# ESP32_mini_4L.net
KiCad netlist of a schematic drawn in EAGLE
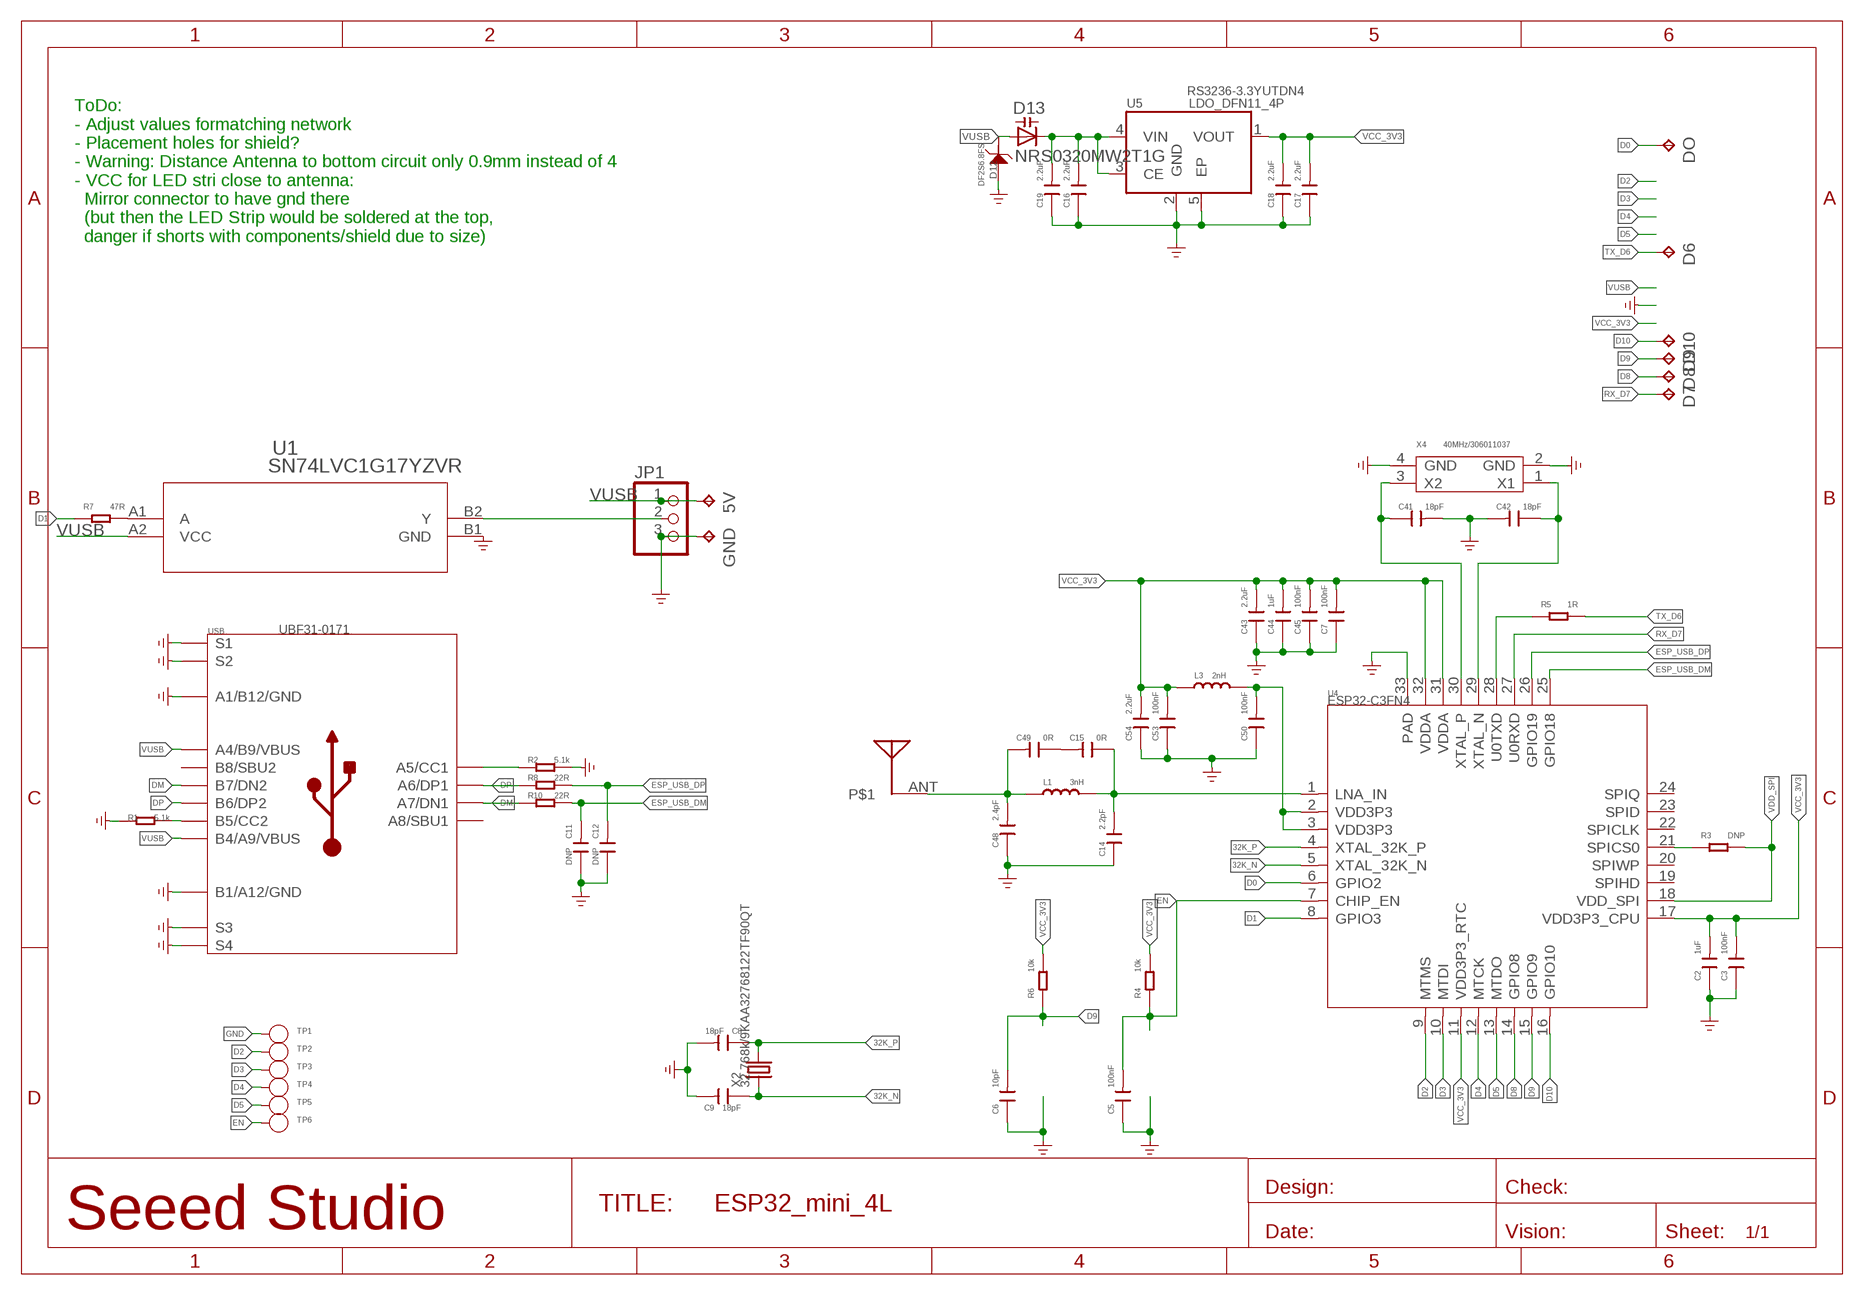
[diagram p0: schematic, sheet 1]

(export (version "E")
  (design (tool "Eeschema 10.0.6"))
  (components
    (comp (ref "5V")
      (value "TPTP07R")
      (footprint "eagle-import:TP07R")
      (libsource (lib "eagle-import") (part "TPTP07R"))
    )
    (comp (ref "C2")
      (value "1uF")
      (footprint "eagle-import:C0201")
      (libsource (lib "eagle-import") (part "CAP-0201"))
    )
    (comp (ref "C3")
      (value "100nF")
      (footprint "eagle-import:C0201")
      (libsource (lib "eagle-import") (part "CAP-0201"))
    )
    (comp (ref "C5")
      (value "100nF")
      (footprint "eagle-import:C0201")
      (libsource (lib "eagle-import") (part "CAP-0201"))
    )
    (comp (ref "C6")
      (value "10pF")
      (footprint "eagle-import:C0201")
      (libsource (lib "eagle-import") (part "CAP-0201"))
    )
    (comp (ref "C7")
      (value "100nF")
      (footprint "eagle-import:C0201")
      (libsource (lib "eagle-import") (part "CAP-0201"))
    )
    (comp (ref "C8")
      (value "18pF")
      (footprint "eagle-import:C0201")
      (libsource (lib "eagle-import") (part "CAP-0201"))
    )
    (comp (ref "C9")
      (value "18pF")
      (footprint "eagle-import:C0201")
      (libsource (lib "eagle-import") (part "CAP-0201"))
    )
    (comp (ref "C11")
      (value "DNP")
      (footprint "eagle-import:C0201")
      (libsource (lib "eagle-import") (part "CAP-0201"))
    )
    (comp (ref "C12")
      (value "DNP")
      (footprint "eagle-import:C0201")
      (libsource (lib "eagle-import") (part "CAP-0201"))
    )
    (comp (ref "C14")
      (value "2.2pF")
      (footprint "eagle-import:C0201")
      (libsource (lib "eagle-import") (part "CAP-0201"))
    )
    (comp (ref "C15")
      (value "0R")
      (footprint "eagle-import:C0201")
      (libsource (lib "eagle-import") (part "CAP-0201"))
    )
    (comp (ref "C16")
      (value "2.2uF")
      (footprint "eagle-import:C0201")
      (libsource (lib "eagle-import") (part "CAP-0201"))
    )
    (comp (ref "C17")
      (value "2.2uF")
      (footprint "eagle-import:C0201")
      (libsource (lib "eagle-import") (part "CAP-0201"))
    )
    (comp (ref "C18")
      (value "2.2uF")
      (footprint "eagle-import:C0201")
      (libsource (lib "eagle-import") (part "CAP-0201"))
    )
    (comp (ref "C19")
      (value "2.2uF")
      (footprint "eagle-import:C0201")
      (libsource (lib "eagle-import") (part "CAP-0201"))
    )
    (comp (ref "C41")
      (value "18pF")
      (footprint "eagle-import:C0201")
      (libsource (lib "eagle-import") (part "CAP-0201"))
    )
    (comp (ref "C42")
      (value "18pF")
      (footprint "eagle-import:C0201")
      (libsource (lib "eagle-import") (part "CAP-0201"))
    )
    (comp (ref "C43")
      (value "2.2uF")
      (footprint "eagle-import:C0201")
      (libsource (lib "eagle-import") (part "CAP-0201"))
    )
    (comp (ref "C44")
      (value "1uF")
      (footprint "eagle-import:C0201")
      (libsource (lib "eagle-import") (part "CAP-0201"))
    )
    (comp (ref "C45")
      (value "100nF")
      (footprint "eagle-import:C0201")
      (libsource (lib "eagle-import") (part "CAP-0201"))
    )
    (comp (ref "C48")
      (value "2.4pF")
      (footprint "eagle-import:C0201")
      (libsource (lib "eagle-import") (part "CAP-0201"))
    )
    (comp (ref "C49")
      (value "0R")
      (footprint "eagle-import:C0201")
      (libsource (lib "eagle-import") (part "CAP-0201"))
    )
    (comp (ref "C50")
      (value "100nF")
      (footprint "eagle-import:C0201")
      (libsource (lib "eagle-import") (part "CAP-0201"))
    )
    (comp (ref "C53")
      (value "100nF")
      (footprint "eagle-import:C0201")
      (libsource (lib "eagle-import") (part "CAP-0201"))
    )
    (comp (ref "C54")
      (value "2.2uF")
      (footprint "eagle-import:C0201")
      (libsource (lib "eagle-import") (part "CAP-0201"))
    )
    (comp (ref "D6")
      (value "TPTP07R")
      (footprint "eagle-import:TP07R")
      (libsource (lib "eagle-import") (part "TPTP07R"))
    )
    (comp (ref "D7")
      (value "TPTP07R")
      (footprint "eagle-import:TP07R")
      (libsource (lib "eagle-import") (part "TPTP07R"))
    )
    (comp (ref "D8")
      (value "TPTP07R")
      (footprint "eagle-import:TP07R")
      (libsource (lib "eagle-import") (part "TPTP07R"))
    )
    (comp (ref "D9")
      (value "TPTP07R")
      (footprint "eagle-import:TP07R")
      (libsource (lib "eagle-import") (part "TPTP07R"))
    )
    (comp (ref "D10")
      (value "TPTP07R")
      (footprint "eagle-import:TP07R")
      (libsource (lib "eagle-import") (part "TPTP07R"))
    )
    (comp (ref "D12")
      (value "DF2S6.8FS")
      (footprint "eagle-import:SOD-923")
      (libsource (lib "eagle-import") (part "D-ESD-2P'DF2S6.8FS'"))
    )
    (comp (ref "D13")
      (value "NRS0320MW2T1G")
      (footprint "eagle-import:SOD523")
      (libsource (lib "eagle-import") (part "DIODE_CAPACITANCE-SOD523"))
    )
    (comp (ref "DO")
      (value "TPTP09R")
      (footprint "eagle-import:TP09R")
      (libsource (lib "eagle-import") (part "TPTP09R"))
    )
    (comp (ref "GND")
      (value "TPTP07R")
      (footprint "eagle-import:TP07R")
      (libsource (lib "eagle-import") (part "TPTP07R"))
    )
    (comp (ref "JP1")
      (value "PINHD-1X3")
      (footprint "eagle-import:1X03")
      (libsource (lib "eagle-import") (part "PINHD-1X3"))
    )
    (comp (ref "L1")
      (value "3nH")
      (footprint "eagle-import:L0201")
      (libsource (lib "eagle-import") (part "INDUCTOR-0201"))
    )
    (comp (ref "L3")
      (value "2nH")
      (footprint "eagle-import:L0201")
      (libsource (lib "eagle-import") (part "INDUCTOR-0201"))
    )
    (comp (ref "R1")
      (value "5.1k")
      (footprint "eagle-import:R0201")
      (libsource (lib "eagle-import") (part "RES-0201"))
    )
    (comp (ref "R2")
      (value "5.1k")
      (footprint "eagle-import:R0201")
      (libsource (lib "eagle-import") (part "RES-0201"))
    )
    (comp (ref "R3")
      (value "DNP")
      (footprint "eagle-import:R0201")
      (libsource (lib "eagle-import") (part "RES-0201"))
    )
    (comp (ref "R4")
      (value "10k")
      (footprint "eagle-import:R0201")
      (libsource (lib "eagle-import") (part "RES-0201"))
    )
    (comp (ref "R5")
      (value "1R")
      (footprint "eagle-import:R0201")
      (libsource (lib "eagle-import") (part "RES-0201"))
    )
    (comp (ref "R6")
      (value "10k")
      (footprint "eagle-import:R0201")
      (libsource (lib "eagle-import") (part "RES-0201"))
    )
    (comp (ref "R7")
      (value "47R")
      (footprint "eagle-import:R0201")
      (libsource (lib "eagle-import") (part "RES-0201"))
    )
    (comp (ref "R8")
      (value "22R")
      (footprint "eagle-import:R0201")
      (libsource (lib "eagle-import") (part "RES-0201"))
    )
    (comp (ref "R10")
      (value "22R")
      (footprint "eagle-import:R0201")
      (libsource (lib "eagle-import") (part "RES-0201"))
    )
    (comp (ref "TP1")
      (value "DNP")
      (footprint "eagle-import:TP_3535")
      (libsource (lib "eagle-import") (part "TEST-POINT-35"))
    )
    (comp (ref "TP2")
      (value "DNP")
      (footprint "eagle-import:TP_3535")
      (libsource (lib "eagle-import") (part "TEST-POINT-35"))
    )
    (comp (ref "TP3")
      (value "DNP")
      (footprint "eagle-import:TP_3535")
      (libsource (lib "eagle-import") (part "TEST-POINT-35"))
    )
    (comp (ref "TP4")
      (value "DNP")
      (footprint "eagle-import:TP_3535")
      (libsource (lib "eagle-import") (part "TEST-POINT-35"))
    )
    (comp (ref "TP5")
      (value "DNP")
      (footprint "eagle-import:TP_3535")
      (libsource (lib "eagle-import") (part "TEST-POINT-35"))
    )
    (comp (ref "TP6")
      (value "DNP")
      (footprint "eagle-import:TP_3535")
      (libsource (lib "eagle-import") (part "TEST-POINT-35"))
    )
    (comp (ref "U$1")
      (value "KH5220-A36KH5220-A36")
      (footprint "eagle-import:KH5220-A36")
      (libsource (lib "eagle-import") (part "KH5220-A36KH5220-A36"))
    )
    (comp (ref "U1")
      (value "SN74LVC1G17YZVR")
      (footprint "eagle-import:YZV4")
      (fields (field (name "COPYRIGHT") "Copyright (C) 2024 Ultra Librarian. All rights reserved."))
      (libsource (lib "eagle-import") (part "SN74LVC1G17YZVR"))
    )
    (comp (ref "U4")
      (value "ESP32-C3FN4")
      (footprint "eagle-import:QFN32G-0.5-5X5MM")
      (libsource (lib "eagle-import") (part "MCU-ESP32-C3"))
    )
    (comp (ref "U5")
      (value "LDO_DFN11_4P")
      (footprint "eagle-import:LDO_DFN1_1_4P")
      (libsource (lib "eagle-import") (part "LDO_DFN11_4P"))
    )
    (comp (ref "USB")
      (value "UBF31-0171")
      (footprint "eagle-import:USB2.0-TYPE-C")
      (libsource (lib "eagle-import") (part "USB2.0-TYPE-C"))
    )
    (comp (ref "X2")
      (value "32.768k/9KAA32768122TF90QT")
      (footprint "eagle-import:X2-SMD-1.6X1.0X0.5MM")
      (libsource (lib "eagle-import") (part "CRYSTAL-2P-1610"))
    )
    (comp (ref "X4")
      (value "40MHz/306011037")
      (footprint "eagle-import:X4-SMD-2.0X1.6X0.5MM")
      (libsource (lib "eagle-import") (part "CRYSTAL-4P-2016"))
    )
  )
  (nets
    (net (code "1") (name "32K_N") (class "Default")
      (node (ref "C9") (pin "1") (pinfunction "1_1") (pintype "passive"))
      (node (ref "U4") (pin "5") (pinfunction "XTAL_32K_N_5") (pintype "bidirectional"))
      (node (ref "X2") (pin "1") (pinfunction "1_1") (pintype "passive"))
    )
    (net (code "2") (name "32K_P") (class "Default")
      (node (ref "C8") (pin "1") (pinfunction "1_1") (pintype "passive"))
      (node (ref "U4") (pin "4") (pinfunction "XTAL_32K_P_4") (pintype "bidirectional"))
      (node (ref "X2") (pin "2") (pinfunction "2_2") (pintype "passive"))
    )
    (net (code "3") (name "D0") (class "Default")
      (node (ref "DO") (pin "TP") (pinfunction "TP_TP") (pintype "input"))
      (node (ref "U4") (pin "6") (pinfunction "GPIO2_6") (pintype "bidirectional"))
    )
    (net (code "4") (name "D1") (class "Default")
      (node (ref "R7") (pin "2") (pinfunction "2_2") (pintype "passive"))
      (node (ref "U4") (pin "8") (pinfunction "GPIO3_8") (pintype "bidirectional"))
    )
    (net (code "5") (name "D2") (class "Default")
      (node (ref "TP2") (pin "T") (pinfunction "T_T") (pintype "bidirectional"))
      (node (ref "U4") (pin "9") (pinfunction "MTMS_9") (pintype "bidirectional"))
    )
    (net (code "6") (name "D3") (class "Default")
      (node (ref "TP3") (pin "T") (pinfunction "T_T") (pintype "bidirectional"))
      (node (ref "U4") (pin "10") (pinfunction "MTDI_10") (pintype "bidirectional"))
    )
    (net (code "7") (name "D4") (class "Default")
      (node (ref "TP4") (pin "T") (pinfunction "T_T") (pintype "bidirectional"))
      (node (ref "U4") (pin "12") (pinfunction "MTCK_12") (pintype "bidirectional"))
    )
    (net (code "8") (name "D5") (class "Default")
      (node (ref "TP5") (pin "T") (pinfunction "T_T") (pintype "bidirectional"))
      (node (ref "U4") (pin "13") (pinfunction "MTDO_13") (pintype "bidirectional"))
    )
    (net (code "9") (name "D8") (class "Default")
      (node (ref "D8") (pin "TP") (pinfunction "TP_TP") (pintype "input"))
      (node (ref "U4") (pin "14") (pinfunction "GPIO8_14") (pintype "bidirectional"))
    )
    (net (code "10") (name "D9") (class "Default")
      (node (ref "C6") (pin "2") (pinfunction "2_2") (pintype "passive"))
      (node (ref "D9") (pin "TP") (pinfunction "TP_TP") (pintype "input"))
      (node (ref "R6") (pin "1") (pinfunction "1_1") (pintype "passive"))
      (node (ref "U4") (pin "15") (pinfunction "GPIO9_15") (pintype "bidirectional"))
    )
    (net (code "11") (name "D10") (class "Default")
      (node (ref "D10") (pin "TP") (pinfunction "TP_TP") (pintype "input"))
      (node (ref "U4") (pin "16") (pinfunction "GPIO10_16") (pintype "bidirectional"))
    )
    (net (code "12") (name "DM") (class "Default")
      (node (ref "R10") (pin "1") (pinfunction "1_1") (pintype "passive"))
      (node (ref "USB") (pin "A7") (pinfunction "A7/DN1_A7") (pintype "bidirectional"))
      (node (ref "USB") (pin "B7") (pinfunction "B7/DN2_B7") (pintype "bidirectional"))
    )
    (net (code "13") (name "DP") (class "Default")
      (node (ref "R8") (pin "1") (pinfunction "1_1") (pintype "passive"))
      (node (ref "USB") (pin "A6") (pinfunction "A6/DP1_A6") (pintype "bidirectional"))
      (node (ref "USB") (pin "B6") (pinfunction "B6/DP2_B6") (pintype "bidirectional"))
    )
    (net (code "14") (name "EN") (class "Default")
      (node (ref "C5") (pin "2") (pinfunction "2_2") (pintype "passive"))
      (node (ref "R4") (pin "1") (pinfunction "1_1") (pintype "passive"))
      (node (ref "TP6") (pin "T") (pinfunction "T_T") (pintype "bidirectional"))
      (node (ref "U4") (pin "7") (pinfunction "CHIP_EN_7") (pintype "bidirectional"))
    )
    (net (code "15") (name "ESP_USB_DM") (class "Default")
      (node (ref "C11") (pin "2") (pinfunction "2_2") (pintype "passive"))
      (node (ref "R10") (pin "2") (pinfunction "2_2") (pintype "passive"))
      (node (ref "U4") (pin "25") (pinfunction "GPIO18_25") (pintype "bidirectional"))
    )
    (net (code "16") (name "ESP_USB_DP") (class "Default")
      (node (ref "C12") (pin "2") (pinfunction "2_2") (pintype "passive"))
      (node (ref "R8") (pin "2") (pinfunction "2_2") (pintype "passive"))
      (node (ref "U4") (pin "26") (pinfunction "GPIO19_26") (pintype "bidirectional"))
    )
    (net (code "17") (name "GND") (class "Default")
      (node (ref "C11") (pin "1") (pinfunction "1_1") (pintype "passive"))
      (node (ref "C12") (pin "1") (pinfunction "1_1") (pintype "passive"))
      (node (ref "C14") (pin "1") (pinfunction "1_1") (pintype "passive"))
      (node (ref "C16") (pin "1") (pinfunction "1_1") (pintype "passive"))
      (node (ref "C17") (pin "1") (pinfunction "1_1") (pintype "passive"))
      (node (ref "C18") (pin "1") (pinfunction "1_1") (pintype "passive"))
      (node (ref "C19") (pin "1") (pinfunction "1_1") (pintype "passive"))
      (node (ref "C2") (pin "1") (pinfunction "1_1") (pintype "passive"))
      (node (ref "C3") (pin "1") (pinfunction "1_1") (pintype "passive"))
      (node (ref "C41") (pin "2") (pinfunction "2_2") (pintype "passive"))
      (node (ref "C42") (pin "2") (pinfunction "2_2") (pintype "passive"))
      (node (ref "C43") (pin "1") (pinfunction "1_1") (pintype "passive"))
      (node (ref "C44") (pin "1") (pinfunction "1_1") (pintype "passive"))
      (node (ref "C45") (pin "1") (pinfunction "1_1") (pintype "passive"))
      (node (ref "C48") (pin "1") (pinfunction "1_1") (pintype "passive"))
      (node (ref "C5") (pin "1") (pinfunction "1_1") (pintype "passive"))
      (node (ref "C50") (pin "1") (pinfunction "1_1") (pintype "passive"))
      (node (ref "C53") (pin "1") (pinfunction "1_1") (pintype "passive"))
      (node (ref "C54") (pin "1") (pinfunction "1_1") (pintype "passive"))
      (node (ref "C6") (pin "1") (pinfunction "1_1") (pintype "passive"))
      (node (ref "C7") (pin "1") (pinfunction "1_1") (pintype "passive"))
      (node (ref "C8") (pin "2") (pinfunction "2_2") (pintype "passive"))
      (node (ref "C9") (pin "2") (pinfunction "2_2") (pintype "passive"))
      (node (ref "D12") (pin "2") (pinfunction "1_2") (pintype "bidirectional"))
      (node (ref "GND") (pin "TP") (pinfunction "TP_TP") (pintype "input"))
      (node (ref "JP1") (pin "3") (pinfunction "3_3") (pintype "passive"))
      (node (ref "R1") (pin "1") (pinfunction "1_1") (pintype "passive"))
      (node (ref "R2") (pin "2") (pinfunction "2_2") (pintype "passive"))
      (node (ref "TP1") (pin "T") (pinfunction "T_T") (pintype "bidirectional"))
      (node (ref "U1") (pin "B1") (pinfunction "GND_B1") (pintype "power_in"))
      (node (ref "U4") (pin "33") (pinfunction "PAD_33") (pintype "bidirectional"))
      (node (ref "U5") (pin "2") (pinfunction "GND_2") (pintype "bidirectional"))
      (node (ref "U5") (pin "5") (pinfunction "EP_5") (pintype "bidirectional"))
      (node (ref "USB") (pin "A1_B12") (pinfunction "A1/B12/GND_A1_B12") (pintype "bidirectional"))
      (node (ref "USB") (pin "B1_A12") (pinfunction "B1/A12/GND_B1_A12") (pintype "bidirectional"))
      (node (ref "USB") (pin "S1") (pinfunction "S1_S1") (pintype "bidirectional"))
      (node (ref "USB") (pin "S2") (pinfunction "S2_S2") (pintype "bidirectional"))
      (node (ref "USB") (pin "S3") (pinfunction "S3_S3") (pintype "bidirectional"))
      (node (ref "USB") (pin "S4") (pinfunction "S4_S4") (pintype "bidirectional"))
      (node (ref "USB") (pin "S5") (pinfunction "S1_S5") (pintype "bidirectional"))
      (node (ref "USB") (pin "S6") (pinfunction "S2_S6") (pintype "bidirectional"))
      (node (ref "X4") (pin "2") (pinfunction "GND_2") (pintype "bidirectional"))
      (node (ref "X4") (pin "4") (pinfunction "GND_4") (pintype "bidirectional"))
    )
    (net (code "18") (name "Net-(C15-Pad2)") (class "Default")
      (node (ref "C15") (pin "2") (pinfunction "2_2") (pintype "passive"))
      (node (ref "C49") (pin "1") (pinfunction "1_1") (pintype "passive"))
    )
    (net (code "19") (name "Net-(C50-Pad2)") (class "Default")
      (node (ref "C50") (pin "2") (pinfunction "2_2") (pintype "passive"))
      (node (ref "L3") (pin "2") (pinfunction "2_2") (pintype "passive"))
      (node (ref "U4") (pin "2") (pinfunction "VDD3P3_2") (pintype "bidirectional"))
      (node (ref "U4") (pin "3") (pinfunction "VDD3P3_3") (pintype "bidirectional"))
    )
    (net (code "20") (name "Net-(U$1-P$1)") (class "Default")
      (node (ref "C48") (pin "2") (pinfunction "2_2") (pintype "passive"))
      (node (ref "C49") (pin "2") (pinfunction "2_2") (pintype "passive"))
      (node (ref "L1") (pin "1") (pinfunction "1_1") (pintype "passive"))
      (node (ref "U$1") (pin "ANT") (pinfunction "P$1_ANT") (pintype "bidirectional"))
    )
    (net (code "21") (name "Net-(U1-A)") (class "Default")
      (node (ref "R7") (pin "1") (pinfunction "1_1") (pintype "passive"))
      (node (ref "U1") (pin "A1") (pinfunction "A_A1") (pintype "input"))
    )
    (net (code "22") (name "Net-(U1-Y)") (class "Default")
      (node (ref "JP1") (pin "2") (pinfunction "2_2") (pintype "passive"))
      (node (ref "U1") (pin "B2") (pinfunction "Y_B2") (pintype "output"))
    )
    (net (code "23") (name "Net-(U4-LNA_IN)") (class "Default")
      (node (ref "C14") (pin "2") (pinfunction "2_2") (pintype "passive"))
      (node (ref "C15") (pin "1") (pinfunction "1_1") (pintype "passive"))
      (node (ref "L1") (pin "2") (pinfunction "2_2") (pintype "passive"))
      (node (ref "U4") (pin "1") (pinfunction "LNA_IN_1") (pintype "bidirectional"))
    )
    (net (code "24") (name "Net-(U4-SPICS0)") (class "Default")
      (node (ref "R3") (pin "1") (pinfunction "1_1") (pintype "passive"))
      (node (ref "U4") (pin "21") (pinfunction "SPICS0_21") (pintype "bidirectional"))
    )
    (net (code "25") (name "Net-(U4-U0TXD)") (class "Default")
      (node (ref "R5") (pin "2") (pinfunction "2_2") (pintype "passive"))
      (node (ref "U4") (pin "28") (pinfunction "U0TXD_28") (pintype "bidirectional"))
    )
    (net (code "26") (name "Net-(U4-XTAL_N)") (class "Default")
      (node (ref "C42") (pin "1") (pinfunction "1_1") (pintype "passive"))
      (node (ref "U4") (pin "29") (pinfunction "XTAL_N_29") (pintype "bidirectional"))
      (node (ref "X4") (pin "1") (pinfunction "X1_1") (pintype "bidirectional"))
    )
    (net (code "27") (name "Net-(U4-XTAL_P)") (class "Default")
      (node (ref "C41") (pin "1") (pinfunction "1_1") (pintype "passive"))
      (node (ref "U4") (pin "30") (pinfunction "XTAL_P_30") (pintype "bidirectional"))
      (node (ref "X4") (pin "3") (pinfunction "X2_3") (pintype "bidirectional"))
    )
    (net (code "28") (name "Net-(U5-CE)") (class "Default")
      (node (ref "C16") (pin "2") (pinfunction "2_2") (pintype "passive"))
      (node (ref "C19") (pin "2") (pinfunction "2_2") (pintype "passive"))
      (node (ref "D13") (pin "C") (pinfunction "C_C") (pintype "passive"))
      (node (ref "U5") (pin "3") (pinfunction "CE_3") (pintype "bidirectional"))
      (node (ref "U5") (pin "4") (pinfunction "VIN_4") (pintype "bidirectional"))
    )
    (net (code "29") (name "Net-(USB-A5{slash}CC1)") (class "Default")
      (node (ref "R2") (pin "1") (pinfunction "1_1") (pintype "passive"))
      (node (ref "USB") (pin "A5") (pinfunction "A5/CC1_A5") (pintype "bidirectional"))
    )
    (net (code "30") (name "Net-(USB-B5{slash}CC2)") (class "Default")
      (node (ref "R1") (pin "2") (pinfunction "2_2") (pintype "passive"))
      (node (ref "USB") (pin "B5") (pinfunction "B5/CC2_B5") (pintype "bidirectional"))
    )
    (net (code "31") (name "RX_D7") (class "Default")
      (node (ref "D7") (pin "TP") (pinfunction "TP_TP") (pintype "input"))
      (node (ref "U4") (pin "27") (pinfunction "U0RXD_27") (pintype "bidirectional"))
    )
    (net (code "32") (name "TX_D6") (class "Default")
      (node (ref "D6") (pin "TP") (pinfunction "TP_TP") (pintype "input"))
      (node (ref "R5") (pin "1") (pinfunction "1_1") (pintype "passive"))
    )
    (net (code "33") (name "VCC_3V3") (class "Default")
      (node (ref "C17") (pin "2") (pinfunction "2_2") (pintype "passive"))
      (node (ref "C18") (pin "2") (pinfunction "2_2") (pintype "passive"))
      (node (ref "C2") (pin "2") (pinfunction "2_2") (pintype "passive"))
      (node (ref "C3") (pin "2") (pinfunction "2_2") (pintype "passive"))
      (node (ref "C43") (pin "2") (pinfunction "2_2") (pintype "passive"))
      (node (ref "C44") (pin "2") (pinfunction "2_2") (pintype "passive"))
      (node (ref "C45") (pin "2") (pinfunction "2_2") (pintype "passive"))
      (node (ref "C53") (pin "2") (pinfunction "2_2") (pintype "passive"))
      (node (ref "C54") (pin "2") (pinfunction "2_2") (pintype "passive"))
      (node (ref "C7") (pin "2") (pinfunction "2_2") (pintype "passive"))
      (node (ref "L3") (pin "1") (pinfunction "1_1") (pintype "passive"))
      (node (ref "R4") (pin "2") (pinfunction "2_2") (pintype "passive"))
      (node (ref "R6") (pin "2") (pinfunction "2_2") (pintype "passive"))
      (node (ref "U4") (pin "11") (pinfunction "VDD3P3_RTC_11") (pintype "bidirectional"))
      (node (ref "U4") (pin "17") (pinfunction "VDD3P3_CPU_17") (pintype "bidirectional"))
      (node (ref "U4") (pin "31") (pinfunction "VDDA_31") (pintype "bidirectional"))
      (node (ref "U4") (pin "32") (pinfunction "VDDA_32") (pintype "bidirectional"))
      (node (ref "U5") (pin "1") (pinfunction "VOUT_1") (pintype "bidirectional"))
    )
    (net (code "34") (name "VDD_SPI") (class "Default")
      (node (ref "R3") (pin "2") (pinfunction "2_2") (pintype "passive"))
      (node (ref "U4") (pin "18") (pinfunction "VDD_SPI_18") (pintype "bidirectional"))
    )
    (net (code "35") (name "VUSB") (class "Default")
      (node (ref "5V") (pin "TP") (pinfunction "TP_TP") (pintype "input"))
      (node (ref "D12") (pin "1") (pinfunction "2_1") (pintype "bidirectional"))
      (node (ref "D13") (pin "A") (pinfunction "A_A") (pintype "passive"))
      (node (ref "JP1") (pin "1") (pinfunction "1_1") (pintype "passive"))
      (node (ref "U1") (pin "A2") (pinfunction "VCC_A2") (pintype "power_in"))
      (node (ref "USB") (pin "A4_B9") (pinfunction "A4/B9/VBUS_A4_B9") (pintype "bidirectional"))
      (node (ref "USB") (pin "B4_A9") (pinfunction "B4/A9/VBUS_B4_A9") (pintype "bidirectional"))
    )
    (net (code "36") (name "unconnected-(U4-SPICLK-Pad22)") (class "Default")
      (node (ref "U4") (pin "22") (pinfunction "SPICLK_22") (pintype "bidirectional"))
    )
    (net (code "37") (name "unconnected-(U4-SPID-Pad23)") (class "Default")
      (node (ref "U4") (pin "23") (pinfunction "SPID_23") (pintype "bidirectional"))
    )
    (net (code "38") (name "unconnected-(U4-SPIHD-Pad19)") (class "Default")
      (node (ref "U4") (pin "19") (pinfunction "SPIHD_19") (pintype "bidirectional"))
    )
    (net (code "39") (name "unconnected-(U4-SPIQ-Pad24)") (class "Default")
      (node (ref "U4") (pin "24") (pinfunction "SPIQ_24") (pintype "bidirectional"))
    )
    (net (code "40") (name "unconnected-(U4-SPIWP-Pad20)") (class "Default")
      (node (ref "U4") (pin "20") (pinfunction "SPIWP_20") (pintype "bidirectional"))
    )
    (net (code "41") (name "unconnected-(USB-A8{slash}SBU1-PadA8)") (class "Default")
      (node (ref "USB") (pin "A8") (pinfunction "A8/SBU1_A8") (pintype "bidirectional"))
    )
    (net (code "42") (name "unconnected-(USB-B8{slash}SBU2-PadB8)") (class "Default")
      (node (ref "USB") (pin "B8") (pinfunction "B8/SBU2_B8") (pintype "bidirectional"))
    )
  )
)
